# El-Fueradoro_Zuendbox_v2.net
KiCad netlist of a schematic drawn in EAGLE
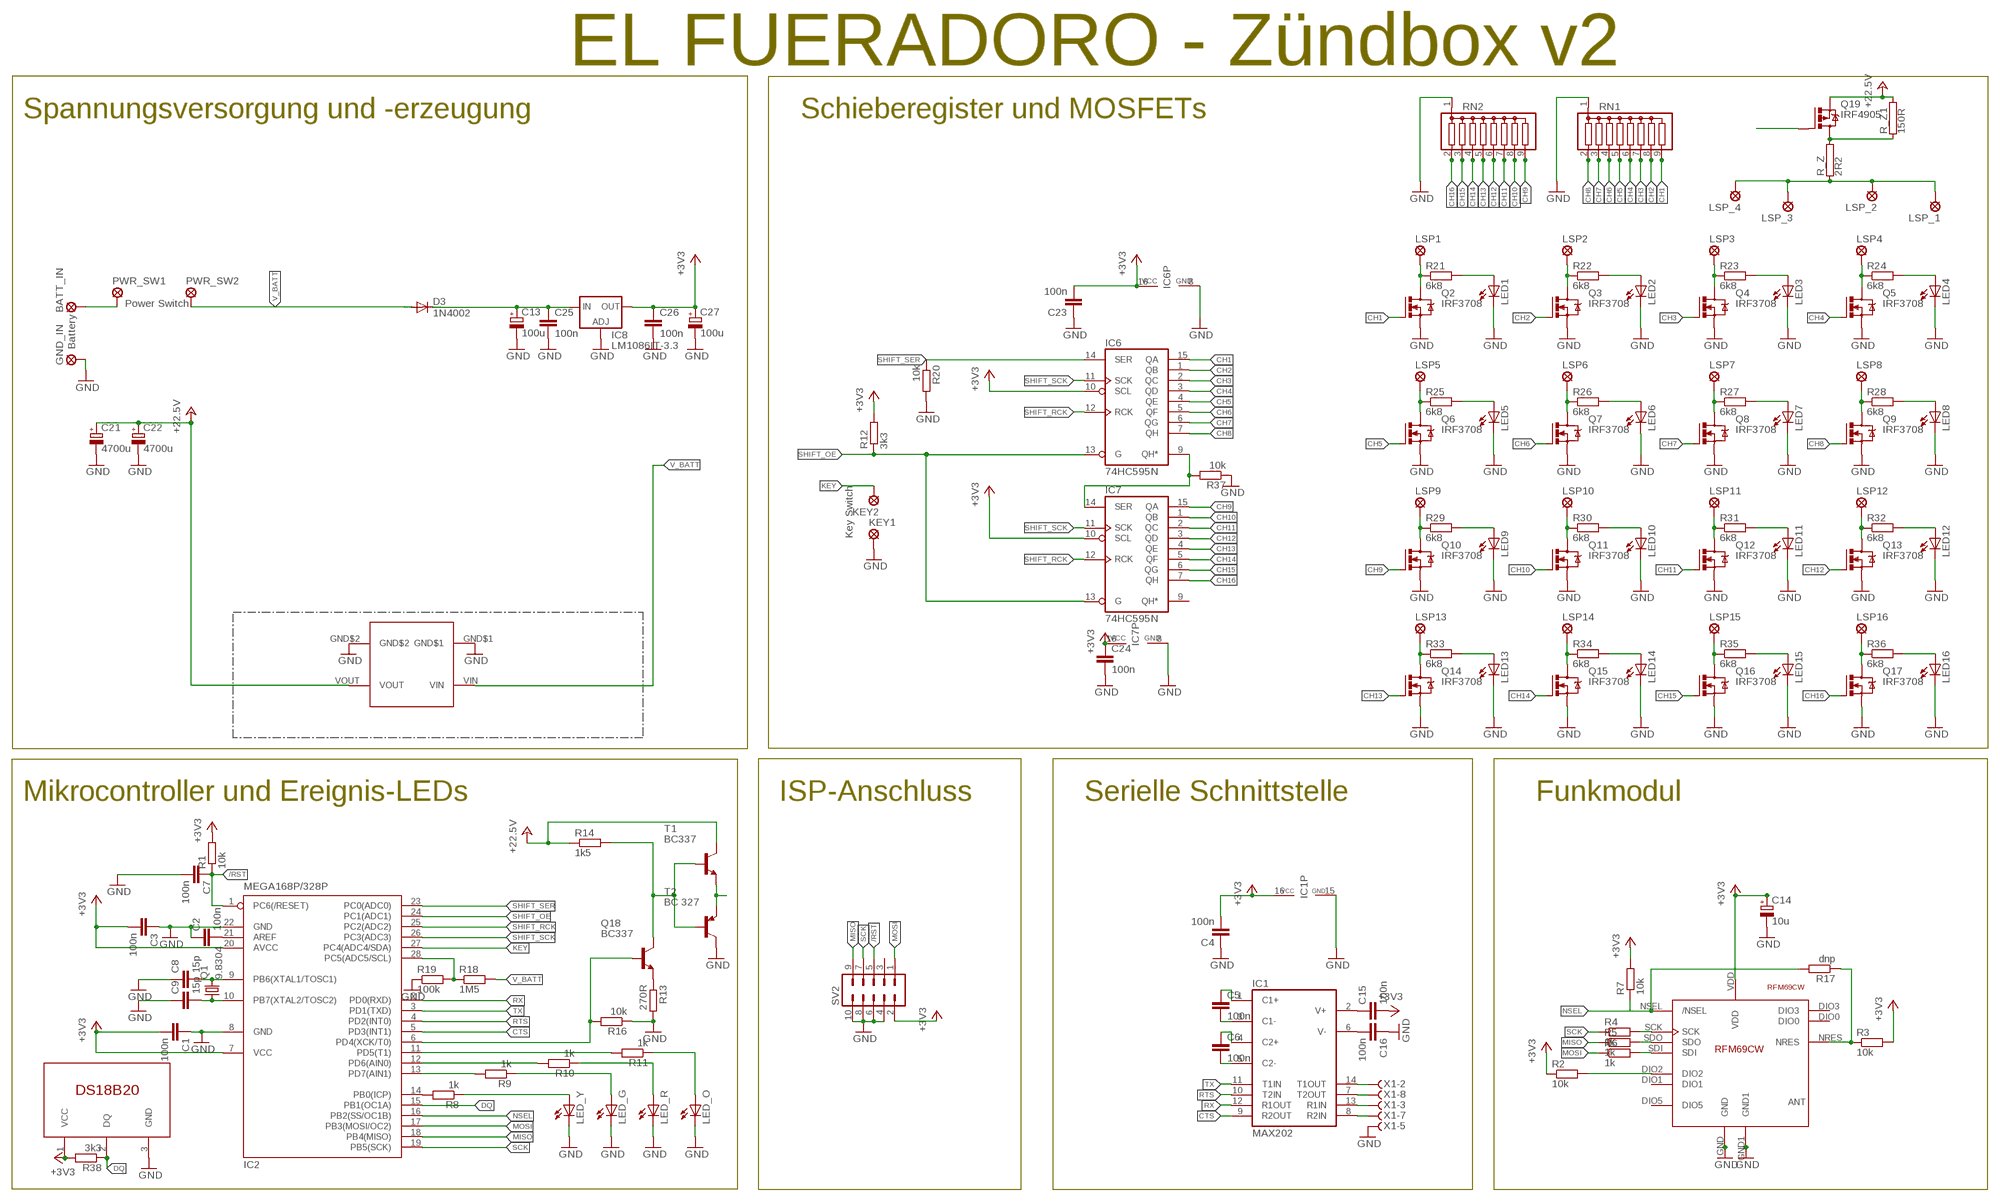
[diagram p0: schematic, sheet 1]

(export (version "E")
  (design (tool "Eeschema 10.0.6"))
  (components
    (comp (ref "BATT_IN")
      (value "LSP10")
      (footprint "eagle-import:LSP10")
      (libsource (lib "eagle-import") (part "LSP10"))
    )
    (comp (ref "C1")
      (value "100n")
      (footprint "eagle-import:C025-024X044")
      (libsource (lib "eagle-import") (part "C-EU025-024X044"))
    )
    (comp (ref "C2")
      (value "100n")
      (footprint "eagle-import:C025-024X044")
      (libsource (lib "eagle-import") (part "C-EU025-024X044"))
    )
    (comp (ref "C3")
      (value "100n")
      (footprint "eagle-import:C025-024X044")
      (libsource (lib "eagle-import") (part "C-EU025-024X044"))
    )
    (comp (ref "C4")
      (value "100n")
      (footprint "eagle-import:C025-024X044")
      (libsource (lib "eagle-import") (part "C-EU025-024X044"))
    )
    (comp (ref "C5")
      (value "100n")
      (footprint "eagle-import:C025-024X044")
      (libsource (lib "eagle-import") (part "C-EU025-024X044"))
    )
    (comp (ref "C6")
      (value "100n")
      (footprint "eagle-import:C025-024X044")
      (libsource (lib "eagle-import") (part "C-EU025-024X044"))
    )
    (comp (ref "C7")
      (value "100n")
      (footprint "eagle-import:C025-024X044")
      (libsource (lib "eagle-import") (part "C-EU025-024X044"))
    )
    (comp (ref "C8")
      (value "15p")
      (footprint "eagle-import:C025-024X044")
      (libsource (lib "eagle-import") (part "C-EU025-024X044"))
    )
    (comp (ref "C9")
      (value "15p")
      (footprint "eagle-import:C025-024X044")
      (libsource (lib "eagle-import") (part "C-EU025-024X044"))
    )
    (comp (ref "C13")
      (value "100u")
      (footprint "eagle-import:B45181A")
      (libsource (lib "eagle-import") (part "CPOL-EUB45181A"))
    )
    (comp (ref "C14")
      (value "10u")
      (footprint "eagle-import:B45181A")
      (libsource (lib "eagle-import") (part "CPOL-EUB45181A"))
    )
    (comp (ref "C15")
      (value "100n")
      (footprint "eagle-import:C025-024X044")
      (libsource (lib "eagle-import") (part "C-EU025-024X044"))
    )
    (comp (ref "C16")
      (value "100n")
      (footprint "eagle-import:C025-024X044")
      (libsource (lib "eagle-import") (part "C-EU025-024X044"))
    )
    (comp (ref "C21")
      (value "4700u")
      (footprint "eagle-import:E7,5-18")
      (libsource (lib "eagle-import") (part "CPOL-EUE7.5-18"))
    )
    (comp (ref "C22")
      (value "4700u")
      (footprint "eagle-import:E7,5-18")
      (libsource (lib "eagle-import") (part "CPOL-EUE7.5-18"))
    )
    (comp (ref "C23")
      (value "100n")
      (footprint "eagle-import:C025-024X044")
      (libsource (lib "eagle-import") (part "C-EU025-024X044"))
    )
    (comp (ref "C24")
      (value "100n")
      (footprint "eagle-import:C025-024X044")
      (libsource (lib "eagle-import") (part "C-EU025-024X044"))
    )
    (comp (ref "C25")
      (value "100n")
      (footprint "eagle-import:C025-024X044")
      (libsource (lib "eagle-import") (part "C-EU025-024X044"))
    )
    (comp (ref "C26")
      (value "100n")
      (footprint "eagle-import:C025-024X044")
      (libsource (lib "eagle-import") (part "C-EU025-024X044"))
    )
    (comp (ref "C27")
      (value "100u")
      (footprint "eagle-import:B45181A")
      (libsource (lib "eagle-import") (part "CPOL-EUB45181A"))
    )
    (comp (ref "D3")
      (value "1N4002")
      (footprint "eagle-import:DO41-10")
      (libsource (lib "eagle-import") (part "1N4004"))
    )
    (comp (ref "GND_IN")
      (value "LSP10")
      (footprint "eagle-import:LSP10")
      (libsource (lib "eagle-import") (part "LSP10"))
    )
    (comp (ref "IC1")
      (value "MAX202")
      (footprint "eagle-import:DIL16")
      (fields (field (name "MF") "MAXIM") (field (name "MPN") "MAX232ACPE+"))
      (libsource (lib "eagle-import") (part "MAX232"))
    )
    (comp (ref "IC2")
      (value "MEGA168P/328P")
      (footprint "eagle-import:DIL28-3")
      (libsource (lib "eagle-import") (part "MEGA8-P"))
    )
    (comp (ref "IC6")
      (value "74HC595N")
      (footprint "eagle-import:DIL16")
      (libsource (lib "eagle-import") (part "74595NHC"))
    )
    (comp (ref "IC7")
      (value "74HC595N")
      (footprint "eagle-import:DIL16")
      (libsource (lib "eagle-import") (part "74595NHC"))
    )
    (comp (ref "IC8")
      (value "LM1086IT-3.3")
      (footprint "eagle-import:TO220L1")
      (libsource (lib "eagle-import") (part "LD117A?V"))
    )
    (comp (ref "KEY1")
      (value "LSP10")
      (footprint "eagle-import:LSP10")
      (libsource (lib "eagle-import") (part "LSP10"))
    )
    (comp (ref "KEY2")
      (value "LSP10")
      (footprint "eagle-import:LSP10")
      (libsource (lib "eagle-import") (part "LSP10"))
    )
    (comp (ref "LED1")
      (value "LED3MM")
      (footprint "eagle-import:LED3MM")
      (libsource (lib "eagle-import") (part "LED3MM"))
    )
    (comp (ref "LED2")
      (value "LED3MM")
      (footprint "eagle-import:LED3MM")
      (libsource (lib "eagle-import") (part "LED3MM"))
    )
    (comp (ref "LED3")
      (value "LED3MM")
      (footprint "eagle-import:LED3MM")
      (libsource (lib "eagle-import") (part "LED3MM"))
    )
    (comp (ref "LED4")
      (value "LED3MM")
      (footprint "eagle-import:LED3MM")
      (libsource (lib "eagle-import") (part "LED3MM"))
    )
    (comp (ref "LED5")
      (value "LED3MM")
      (footprint "eagle-import:LED3MM")
      (libsource (lib "eagle-import") (part "LED3MM"))
    )
    (comp (ref "LED6")
      (value "LED3MM")
      (footprint "eagle-import:LED3MM")
      (libsource (lib "eagle-import") (part "LED3MM"))
    )
    (comp (ref "LED7")
      (value "LED3MM")
      (footprint "eagle-import:LED3MM")
      (libsource (lib "eagle-import") (part "LED3MM"))
    )
    (comp (ref "LED8")
      (value "LED3MM")
      (footprint "eagle-import:LED3MM")
      (libsource (lib "eagle-import") (part "LED3MM"))
    )
    (comp (ref "LED9")
      (value "LED3MM")
      (footprint "eagle-import:LED3MM")
      (libsource (lib "eagle-import") (part "LED3MM"))
    )
    (comp (ref "LED10")
      (value "LED3MM")
      (footprint "eagle-import:LED3MM")
      (libsource (lib "eagle-import") (part "LED3MM"))
    )
    (comp (ref "LED11")
      (value "LED3MM")
      (footprint "eagle-import:LED3MM")
      (libsource (lib "eagle-import") (part "LED3MM"))
    )
    (comp (ref "LED12")
      (value "LED3MM")
      (footprint "eagle-import:LED3MM")
      (libsource (lib "eagle-import") (part "LED3MM"))
    )
    (comp (ref "LED13")
      (value "LED3MM")
      (footprint "eagle-import:LED3MM")
      (libsource (lib "eagle-import") (part "LED3MM"))
    )
    (comp (ref "LED14")
      (value "LED3MM")
      (footprint "eagle-import:LED3MM")
      (libsource (lib "eagle-import") (part "LED3MM"))
    )
    (comp (ref "LED15")
      (value "LED3MM")
      (footprint "eagle-import:LED3MM")
      (libsource (lib "eagle-import") (part "LED3MM"))
    )
    (comp (ref "LED16")
      (value "LED3MM")
      (footprint "eagle-import:LED3MM")
      (libsource (lib "eagle-import") (part "LED3MM"))
    )
    (comp (ref "LED_G")
      (value "LED5MM")
      (footprint "eagle-import:LED5MM")
      (libsource (lib "eagle-import") (part "LED5MM"))
    )
    (comp (ref "LED_O")
      (value "LED5MM")
      (footprint "eagle-import:LED5MM")
      (libsource (lib "eagle-import") (part "LED5MM"))
    )
    (comp (ref "LED_R")
      (value "LED5MM")
      (footprint "eagle-import:LED5MM")
      (libsource (lib "eagle-import") (part "LED5MM"))
    )
    (comp (ref "LED_Y")
      (value "LED5MM")
      (footprint "eagle-import:LED5MM")
      (libsource (lib "eagle-import") (part "LED5MM"))
    )
    (comp (ref "LSP1")
      (value "CH1")
      (footprint "eagle-import:LSP11")
      (libsource (lib "eagle-import") (part "LSP11"))
    )
    (comp (ref "LSP2")
      (value "CH2")
      (footprint "eagle-import:LSP11")
      (libsource (lib "eagle-import") (part "LSP11"))
    )
    (comp (ref "LSP3")
      (value "CH3")
      (footprint "eagle-import:LSP11")
      (libsource (lib "eagle-import") (part "LSP11"))
    )
    (comp (ref "LSP4")
      (value "CH4")
      (footprint "eagle-import:LSP11")
      (libsource (lib "eagle-import") (part "LSP11"))
    )
    (comp (ref "LSP5")
      (value "CH5")
      (footprint "eagle-import:LSP11")
      (libsource (lib "eagle-import") (part "LSP11"))
    )
    (comp (ref "LSP6")
      (value "CH6")
      (footprint "eagle-import:LSP11")
      (libsource (lib "eagle-import") (part "LSP11"))
    )
    (comp (ref "LSP7")
      (value "CH7")
      (footprint "eagle-import:LSP11")
      (libsource (lib "eagle-import") (part "LSP11"))
    )
    (comp (ref "LSP8")
      (value "CH8")
      (footprint "eagle-import:LSP11")
      (libsource (lib "eagle-import") (part "LSP11"))
    )
    (comp (ref "LSP9")
      (value "CH9")
      (footprint "eagle-import:LSP11")
      (libsource (lib "eagle-import") (part "LSP11"))
    )
    (comp (ref "LSP10")
      (value "CH10")
      (footprint "eagle-import:LSP11")
      (libsource (lib "eagle-import") (part "LSP11"))
    )
    (comp (ref "LSP11")
      (value "CH11")
      (footprint "eagle-import:LSP11")
      (libsource (lib "eagle-import") (part "LSP11"))
    )
    (comp (ref "LSP12")
      (value "CH12")
      (footprint "eagle-import:LSP11")
      (libsource (lib "eagle-import") (part "LSP11"))
    )
    (comp (ref "LSP13")
      (value "CH13")
      (footprint "eagle-import:LSP11")
      (libsource (lib "eagle-import") (part "LSP11"))
    )
    (comp (ref "LSP14")
      (value "CH14")
      (footprint "eagle-import:LSP11")
      (libsource (lib "eagle-import") (part "LSP11"))
    )
    (comp (ref "LSP15")
      (value "CH15")
      (footprint "eagle-import:LSP11")
      (libsource (lib "eagle-import") (part "LSP11"))
    )
    (comp (ref "LSP16")
      (value "CH16")
      (footprint "eagle-import:LSP11")
      (libsource (lib "eagle-import") (part "LSP11"))
    )
    (comp (ref "LSP_1")
      (value "LSP11")
      (footprint "eagle-import:LSP11")
      (libsource (lib "eagle-import") (part "LSP11"))
    )
    (comp (ref "LSP_2")
      (value "LSP11")
      (footprint "eagle-import:LSP11")
      (libsource (lib "eagle-import") (part "LSP11"))
    )
    (comp (ref "LSP_3")
      (value "LSP11")
      (footprint "eagle-import:LSP11")
      (libsource (lib "eagle-import") (part "LSP11"))
    )
    (comp (ref "LSP_4")
      (value "LSP11")
      (footprint "eagle-import:LSP11")
      (libsource (lib "eagle-import") (part "LSP11"))
    )
    (comp (ref "PWR_SW1")
      (value "LSP10")
      (footprint "eagle-import:LSP10")
      (libsource (lib "eagle-import") (part "LSP10"))
    )
    (comp (ref "PWR_SW2")
      (value "LSP10")
      (footprint "eagle-import:LSP10")
      (libsource (lib "eagle-import") (part "LSP10"))
    )
    (comp (ref "Q1")
      (value "9.8304")
      (footprint "eagle-import:HC49_S")
      (libsource (lib "eagle-import") (part "CRYSTALHC49S"))
    )
    (comp (ref "Q2")
      (value "IRF3708")
      (footprint "eagle-import:TO220BV")
      (libsource (lib "eagle-import") (part "IRF530"))
    )
    (comp (ref "Q3")
      (value "IRF3708")
      (footprint "eagle-import:TO220BV")
      (libsource (lib "eagle-import") (part "IRF530"))
    )
    (comp (ref "Q4")
      (value "IRF3708")
      (footprint "eagle-import:TO220BV")
      (libsource (lib "eagle-import") (part "IRF530"))
    )
    (comp (ref "Q5")
      (value "IRF3708")
      (footprint "eagle-import:TO220BV")
      (libsource (lib "eagle-import") (part "IRF530"))
    )
    (comp (ref "Q6")
      (value "IRF3708")
      (footprint "eagle-import:TO220BV")
      (libsource (lib "eagle-import") (part "IRF530"))
    )
    (comp (ref "Q7")
      (value "IRF3708")
      (footprint "eagle-import:TO220BV")
      (libsource (lib "eagle-import") (part "IRF530"))
    )
    (comp (ref "Q8")
      (value "IRF3708")
      (footprint "eagle-import:TO220BV")
      (libsource (lib "eagle-import") (part "IRF530"))
    )
    (comp (ref "Q9")
      (value "IRF3708")
      (footprint "eagle-import:TO220BV")
      (libsource (lib "eagle-import") (part "IRF530"))
    )
    (comp (ref "Q10")
      (value "IRF3708")
      (footprint "eagle-import:TO220BV")
      (libsource (lib "eagle-import") (part "IRF530"))
    )
    (comp (ref "Q11")
      (value "IRF3708")
      (footprint "eagle-import:TO220BV")
      (libsource (lib "eagle-import") (part "IRF530"))
    )
    (comp (ref "Q12")
      (value "IRF3708")
      (footprint "eagle-import:TO220BV")
      (libsource (lib "eagle-import") (part "IRF530"))
    )
    (comp (ref "Q13")
      (value "IRF3708")
      (footprint "eagle-import:TO220BV")
      (libsource (lib "eagle-import") (part "IRF530"))
    )
    (comp (ref "Q14")
      (value "IRF3708")
      (footprint "eagle-import:TO220BV")
      (libsource (lib "eagle-import") (part "IRF530"))
    )
    (comp (ref "Q15")
      (value "IRF3708")
      (footprint "eagle-import:TO220BV")
      (libsource (lib "eagle-import") (part "IRF530"))
    )
    (comp (ref "Q16")
      (value "IRF3708")
      (footprint "eagle-import:TO220BV")
      (libsource (lib "eagle-import") (part "IRF530"))
    )
    (comp (ref "Q17")
      (value "IRF3708")
      (footprint "eagle-import:TO220BV")
      (libsource (lib "eagle-import") (part "IRF530"))
    )
    (comp (ref "Q18")
      (value "BC337")
      (footprint "eagle-import:TO92")
      (libsource (lib "eagle-import") (part "BC337-40"))
    )
    (comp (ref "Q19")
      (value "IRF4905")
      (footprint "eagle-import:TO220BV")
      (libsource (lib "eagle-import") (part "IRF9530"))
    )
    (comp (ref "R1")
      (value "10k")
      (footprint "eagle-import:0207_10")
      (libsource (lib "eagle-import") (part "R-EU_0207/10"))
    )
    (comp (ref "R2")
      (value "10k")
      (footprint "eagle-import:0207_10")
      (libsource (lib "eagle-import") (part "R-EU_0207/10"))
    )
    (comp (ref "R3")
      (value "10k")
      (footprint "eagle-import:0207_10")
      (libsource (lib "eagle-import") (part "R-EU_0207/10"))
    )
    (comp (ref "R4")
      (value "1k")
      (footprint "eagle-import:0207_10")
      (libsource (lib "eagle-import") (part "R-EU_0207/10"))
    )
    (comp (ref "R5")
      (value "1k")
      (footprint "eagle-import:0207_10")
      (libsource (lib "eagle-import") (part "R-EU_0207/10"))
    )
    (comp (ref "R6")
      (value "1k")
      (footprint "eagle-import:0207_10")
      (libsource (lib "eagle-import") (part "R-EU_0207/10"))
    )
    (comp (ref "R7")
      (value "10k")
      (footprint "eagle-import:0207_10")
      (libsource (lib "eagle-import") (part "R-EU_0207/10"))
    )
    (comp (ref "R8")
      (value "1k")
      (footprint "eagle-import:0207_10")
      (libsource (lib "eagle-import") (part "R-EU_0207/10"))
    )
    (comp (ref "R9")
      (value "1k")
      (footprint "eagle-import:0207_10")
      (libsource (lib "eagle-import") (part "R-EU_0207/10"))
    )
    (comp (ref "R10")
      (value "1k")
      (footprint "eagle-import:0207_10")
      (libsource (lib "eagle-import") (part "R-EU_0207/10"))
    )
    (comp (ref "R11")
      (value "1k")
      (footprint "eagle-import:0207_10")
      (libsource (lib "eagle-import") (part "R-EU_0207/10"))
    )
    (comp (ref "R12")
      (value "3k3")
      (footprint "eagle-import:0207_10")
      (libsource (lib "eagle-import") (part "R-EU_0207/10"))
    )
    (comp (ref "R13")
      (value "270R")
      (footprint "eagle-import:0207_10")
      (libsource (lib "eagle-import") (part "R-EU_0207/10"))
    )
    (comp (ref "R14")
      (value "1k5")
      (footprint "eagle-import:0207_10")
      (libsource (lib "eagle-import") (part "R-EU_0207/10"))
    )
    (comp (ref "R16")
      (value "10k")
      (footprint "eagle-import:0207_10")
      (libsource (lib "eagle-import") (part "R-EU_0207/10"))
    )
    (comp (ref "R17")
      (value "dnp")
      (footprint "eagle-import:0207_10")
      (libsource (lib "eagle-import") (part "R-EU_0207/10"))
    )
    (comp (ref "R18")
      (value "1M5")
      (footprint "eagle-import:0207_10")
      (libsource (lib "eagle-import") (part "R-EU_0207/10"))
    )
    (comp (ref "R19")
      (value "100k")
      (footprint "eagle-import:0207_10")
      (libsource (lib "eagle-import") (part "R-EU_0207/10"))
    )
    (comp (ref "R20")
      (value "10k")
      (footprint "eagle-import:0207_10")
      (libsource (lib "eagle-import") (part "R-EU_0207/10"))
    )
    (comp (ref "R21")
      (value "6k8")
      (footprint "eagle-import:0207_10")
      (libsource (lib "eagle-import") (part "R-EU_0207/10"))
    )
    (comp (ref "R22")
      (value "6k8")
      (footprint "eagle-import:0207_10")
      (libsource (lib "eagle-import") (part "R-EU_0207/10"))
    )
    (comp (ref "R23")
      (value "6k8")
      (footprint "eagle-import:0207_10")
      (libsource (lib "eagle-import") (part "R-EU_0207/10"))
    )
    (comp (ref "R24")
      (value "6k8")
      (footprint "eagle-import:0207_10")
      (libsource (lib "eagle-import") (part "R-EU_0207/10"))
    )
    (comp (ref "R25")
      (value "6k8")
      (footprint "eagle-import:0207_10")
      (libsource (lib "eagle-import") (part "R-EU_0207/10"))
    )
    (comp (ref "R26")
      (value "6k8")
      (footprint "eagle-import:0207_10")
      (libsource (lib "eagle-import") (part "R-EU_0207/10"))
    )
    (comp (ref "R27")
      (value "6k8")
      (footprint "eagle-import:0207_10")
      (libsource (lib "eagle-import") (part "R-EU_0207/10"))
    )
    (comp (ref "R28")
      (value "6k8")
      (footprint "eagle-import:0207_10")
      (libsource (lib "eagle-import") (part "R-EU_0207/10"))
    )
    (comp (ref "R29")
      (value "6k8")
      (footprint "eagle-import:0207_10")
      (libsource (lib "eagle-import") (part "R-EU_0207/10"))
    )
    (comp (ref "R30")
      (value "6k8")
      (footprint "eagle-import:0207_10")
      (libsource (lib "eagle-import") (part "R-EU_0207/10"))
    )
    (comp (ref "R31")
      (value "6k8")
      (footprint "eagle-import:0207_10")
      (libsource (lib "eagle-import") (part "R-EU_0207/10"))
    )
    (comp (ref "R32")
      (value "6k8")
      (footprint "eagle-import:0207_10")
      (libsource (lib "eagle-import") (part "R-EU_0207/10"))
    )
    (comp (ref "R33")
      (value "6k8")
      (footprint "eagle-import:0207_10")
      (libsource (lib "eagle-import") (part "R-EU_0207/10"))
    )
    (comp (ref "R34")
      (value "6k8")
      (footprint "eagle-import:0207_10")
      (libsource (lib "eagle-import") (part "R-EU_0207/10"))
    )
    (comp (ref "R35")
      (value "6k8")
      (footprint "eagle-import:0207_10")
      (libsource (lib "eagle-import") (part "R-EU_0207/10"))
    )
    (comp (ref "R36")
      (value "6k8")
      (footprint "eagle-import:0207_10")
      (libsource (lib "eagle-import") (part "R-EU_0207/10"))
    )
    (comp (ref "R37")
      (value "10k")
      (footprint "eagle-import:0207_10")
      (libsource (lib "eagle-import") (part "R-EU_0207/10"))
    )
    (comp (ref "R38")
      (value "3k3")
      (footprint "eagle-import:0207_10")
      (libsource (lib "eagle-import") (part "R-EU_0207/10"))
    )
    (comp (ref "RN1")
      (value "G08R")
      (footprint "eagle-import:SIL9")
      (libsource (lib "eagle-import") (part "G08R"))
    )
    (comp (ref "RN2")
      (value "G08R")
      (footprint "eagle-import:SIL9")
      (libsource (lib "eagle-import") (part "G08R"))
    )
    (comp (ref "R_Z")
      (value "2R2")
      (footprint "eagle-import:KH214R-8")
      (libsource (lib "eagle-import") (part "RKH214-8R"))
    )
    (comp (ref "R_Z1")
      (value "150R")
      (footprint "eagle-import:KH214R-8")
      (libsource (lib "eagle-import") (part "RKH214-8R"))
    )
    (comp (ref "SV2")
      (value "ML10")
      (footprint "eagle-import:ML10")
      (libsource (lib "eagle-import") (part "ML10"))
    )
    (comp (ref "T1")
      (value "BC337")
      (footprint "eagle-import:TO92")
      (libsource (lib "eagle-import") (part "BC337"))
    )
    (comp (ref "T2")
      (value "BC 327")
      (footprint "eagle-import:TO92")
      (libsource (lib "eagle-import") (part "BC327"))
    )
    (comp (ref "U$2")
      (value "DS18B20")
      (footprint "eagle-import:TO92-LINE")
      (libsource (lib "eagle-import") (part "DS18B20"))
    )
    (comp (ref "U$3")
      (value "XL6009_MODULED")
      (footprint "eagle-import:XL6009_PACK")
      (libsource (lib "eagle-import") (part "XL6009_MODULED"))
    )
    (comp (ref "U$4")
      (value "RFM69CW")
      (footprint "eagle-import:RFM69CW")
      (libsource (lib "eagle-import") (part "RFM69CW"))
    )
    (comp (ref "X1")
      (value "F09HPS")
      (footprint "eagle-import:F09HP")
      (libsource (lib "eagle-import") (part "F09HPS"))
    )
  )
  (nets
    (net (code "1") (name "+3V3") (class "Default")
      (node (ref "C1") (pin "2") (pinfunction "2_2") (pintype "passive"))
      (node (ref "C14") (pin "+") (pinfunction "+_+") (pintype "passive"))
      (node (ref "C15") (pin "2") (pinfunction "2_2") (pintype "passive"))
      (node (ref "C23") (pin "2") (pinfunction "2_2") (pintype "passive"))
      (node (ref "C24") (pin "1") (pinfunction "1_1") (pintype "passive"))
      (node (ref "C26") (pin "1") (pinfunction "1_1") (pintype "passive"))
      (node (ref "C27") (pin "+") (pinfunction "+_+") (pintype "passive"))
      (node (ref "C3") (pin "2") (pinfunction "2_2") (pintype "passive"))
      (node (ref "C4") (pin "2") (pinfunction "2_2") (pintype "passive"))
      (node (ref "IC1") (pin "16") (pinfunction "VCC_16") (pintype "power_in"))
      (node (ref "IC2") (pin "20") (pinfunction "AVCC_20") (pintype "power_in"))
      (node (ref "IC2") (pin "7") (pinfunction "VCC_7") (pintype "power_in"))
      (node (ref "IC6") (pin "10") (pinfunction "SCL_10") (pintype "input"))
      (node (ref "IC6") (pin "16") (pinfunction "VCC_16") (pintype "power_in"))
      (node (ref "IC7") (pin "10") (pinfunction "SCL_10") (pintype "input"))
      (node (ref "IC7") (pin "16") (pinfunction "VCC_16") (pintype "power_in"))
      (node (ref "IC8") (pin "2") (pinfunction "OUT_2") (pintype "passive"))
      (node (ref "R1") (pin "2") (pinfunction "2_2") (pintype "passive"))
      (node (ref "R12") (pin "2") (pinfunction "2_2") (pintype "passive"))
      (node (ref "R2") (pin "1") (pinfunction "1_1") (pintype "passive"))
      (node (ref "R3") (pin "2") (pinfunction "2_2") (pintype "passive"))
      (node (ref "R38") (pin "2") (pinfunction "2_2") (pintype "passive"))
      (node (ref "R7") (pin "2") (pinfunction "2_2") (pintype "passive"))
      (node (ref "SV2") (pin "2") (pinfunction "2_2") (pintype "passive"))
      (node (ref "U$2") (pin "1") (pinfunction "VCC_1") (pintype "power_in"))
      (node (ref "U$4") (pin "VDD") (pinfunction "VDD_VDD") (pintype "power_in"))
    )
    (net (code "2") (name "+22.5V") (class "Default")
      (node (ref "C21") (pin "+") (pinfunction "+_+") (pintype "passive"))
      (node (ref "C22") (pin "+") (pinfunction "+_+") (pintype "passive"))
      (node (ref "Q19") (pin "S") (pinfunction "S_S") (pintype "passive"))
      (node (ref "R14") (pin "1") (pinfunction "1_1") (pintype "passive"))
      (node (ref "R_Z1") (pin "2") (pinfunction "2_2") (pintype "passive"))
      (node (ref "T1") (pin "3") (pinfunction "C_3") (pintype "passive"))
      (node (ref "U$3") (pin "VOUT") (pinfunction "VOUT_VOUT") (pintype "bidirectional"))
    )
    (net (code "3") (name "/PMOSG") (class "Default")
      (node (ref "Q19") (pin "G") (pinfunction "G_G") (pintype "passive"))
      (node (ref "T1") (pin "1") (pinfunction "E_1") (pintype "passive"))
      (node (ref "T2") (pin "1") (pinfunction "E_1") (pintype "passive"))
    )
    (net (code "4") (name "CH1") (class "Default")
      (node (ref "IC6") (pin "15") (pinfunction "QA_15") (pintype "tri_state"))
      (node (ref "Q2") (pin "G") (pinfunction "G_G") (pintype "passive"))
      (node (ref "RN1") (pin "9") (pinfunction "9_9") (pintype "passive"))
    )
    (net (code "5") (name "CH2") (class "Default")
      (node (ref "IC6") (pin "1") (pinfunction "QB_1") (pintype "tri_state"))
      (node (ref "Q3") (pin "G") (pinfunction "G_G") (pintype "passive"))
      (node (ref "RN1") (pin "8") (pinfunction "8_8") (pintype "passive"))
    )
    (net (code "6") (name "CH3") (class "Default")
      (node (ref "IC6") (pin "2") (pinfunction "QC_2") (pintype "tri_state"))
      (node (ref "Q4") (pin "G") (pinfunction "G_G") (pintype "passive"))
      (node (ref "RN1") (pin "7") (pinfunction "7_7") (pintype "passive"))
    )
    (net (code "7") (name "CH4") (class "Default")
      (node (ref "IC6") (pin "3") (pinfunction "QD_3") (pintype "tri_state"))
      (node (ref "Q5") (pin "G") (pinfunction "G_G") (pintype "passive"))
      (node (ref "RN1") (pin "6") (pinfunction "6_6") (pintype "passive"))
    )
    (net (code "8") (name "CH5") (class "Default")
      (node (ref "IC6") (pin "4") (pinfunction "QE_4") (pintype "tri_state"))
      (node (ref "Q6") (pin "G") (pinfunction "G_G") (pintype "passive"))
      (node (ref "RN1") (pin "5") (pinfunction "5_5") (pintype "passive"))
    )
    (net (code "9") (name "CH6") (class "Default")
      (node (ref "IC6") (pin "5") (pinfunction "QF_5") (pintype "tri_state"))
      (node (ref "Q7") (pin "G") (pinfunction "G_G") (pintype "passive"))
      (node (ref "RN1") (pin "4") (pinfunction "4_4") (pintype "passive"))
    )
    (net (code "10") (name "CH7") (class "Default")
      (node (ref "IC6") (pin "6") (pinfunction "QG_6") (pintype "tri_state"))
      (node (ref "Q8") (pin "G") (pinfunction "G_G") (pintype "passive"))
      (node (ref "RN1") (pin "3") (pinfunction "3_3") (pintype "passive"))
    )
    (net (code "11") (name "CH8") (class "Default")
      (node (ref "IC6") (pin "7") (pinfunction "QH_7") (pintype "tri_state"))
      (node (ref "Q9") (pin "G") (pinfunction "G_G") (pintype "passive"))
      (node (ref "RN1") (pin "2") (pinfunction "2_2") (pintype "passive"))
    )
    (net (code "12") (name "CH9") (class "Default")
      (node (ref "IC7") (pin "15") (pinfunction "QA_15") (pintype "tri_state"))
      (node (ref "Q10") (pin "G") (pinfunction "G_G") (pintype "passive"))
      (node (ref "RN2") (pin "9") (pinfunction "9_9") (pintype "passive"))
    )
    (net (code "13") (name "CH10") (class "Default")
      (node (ref "IC7") (pin "1") (pinfunction "QB_1") (pintype "tri_state"))
      (node (ref "Q11") (pin "G") (pinfunction "G_G") (pintype "passive"))
      (node (ref "RN2") (pin "8") (pinfunction "8_8") (pintype "passive"))
    )
    (net (code "14") (name "CH11") (class "Default")
      (node (ref "IC7") (pin "2") (pinfunction "QC_2") (pintype "tri_state"))
      (node (ref "Q12") (pin "G") (pinfunction "G_G") (pintype "passive"))
      (node (ref "RN2") (pin "7") (pinfunction "7_7") (pintype "passive"))
    )
    (net (code "15") (name "CH12") (class "Default")
      (node (ref "IC7") (pin "3") (pinfunction "QD_3") (pintype "tri_state"))
      (node (ref "Q13") (pin "G") (pinfunction "G_G") (pintype "passive"))
      (node (ref "RN2") (pin "6") (pinfunction "6_6") (pintype "passive"))
    )
    (net (code "16") (name "CH13") (class "Default")
      (node (ref "IC7") (pin "4") (pinfunction "QE_4") (pintype "tri_state"))
      (node (ref "Q14") (pin "G") (pinfunction "G_G") (pintype "passive"))
      (node (ref "RN2") (pin "5") (pinfunction "5_5") (pintype "passive"))
    )
    (net (code "17") (name "CH14") (class "Default")
      (node (ref "IC7") (pin "5") (pinfunction "QF_5") (pintype "tri_state"))
      (node (ref "Q15") (pin "G") (pinfunction "G_G") (pintype "passive"))
      (node (ref "RN2") (pin "4") (pinfunction "4_4") (pintype "passive"))
    )
    (net (code "18") (name "CH15") (class "Default")
      (node (ref "IC7") (pin "6") (pinfunction "QG_6") (pintype "tri_state"))
      (node (ref "Q16") (pin "G") (pinfunction "G_G") (pintype "passive"))
      (node (ref "RN2") (pin "3") (pinfunction "3_3") (pintype "passive"))
    )
    (net (code "19") (name "CH16") (class "Default")
      (node (ref "IC7") (pin "7") (pinfunction "QH_7") (pintype "tri_state"))
      (node (ref "Q17") (pin "G") (pinfunction "G_G") (pintype "passive"))
      (node (ref "RN2") (pin "2") (pinfunction "2_2") (pintype "passive"))
    )
    (net (code "20") (name "CTS") (class "Default")
      (node (ref "IC1") (pin "9") (pinfunction "R2OUT_9") (pintype "output"))
      (node (ref "IC2") (pin "5") (pinfunction "PD3(INT1)_5") (pintype "bidirectional"))
    )
    (net (code "21") (name "DQ") (class "Default")
      (node (ref "IC2") (pin "15") (pinfunction "PB1(OC1A)_15") (pintype "bidirectional"))
      (node (ref "R38") (pin "1") (pinfunction "1_1") (pintype "passive"))
      (node (ref "U$2") (pin "2") (pinfunction "DQ_2") (pintype "bidirectional"))
    )
    (net (code "22") (name "GND") (class "Default")
      (node (ref "C1") (pin "1") (pinfunction "1_1") (pintype "passive"))
      (node (ref "C13") (pin "-") (pinfunction "-_-") (pintype "passive"))
      (node (ref "C14") (pin "-") (pinfunction "-_-") (pintype "passive"))
      (node (ref "C16") (pin "1") (pinfunction "1_1") (pintype "passive"))
      (node (ref "C2") (pin "1") (pinfunction "1_1") (pintype "passive"))
      (node (ref "C21") (pin "-") (pinfunction "-_-") (pintype "passive"))
      (node (ref "C22") (pin "-") (pinfunction "-_-") (pintype "passive"))
      (node (ref "C23") (pin "1") (pinfunction "1_1") (pintype "passive"))
      (node (ref "C24") (pin "2") (pinfunction "2_2") (pintype "passive"))
      (node (ref "C25") (pin "2") (pinfunction "2_2") (pintype "passive"))
      (node (ref "C26") (pin "2") (pinfunction "2_2") (pintype "passive"))
      (node (ref "C27") (pin "-") (pinfunction "-_-") (pintype "passive"))
      (node (ref "C3") (pin "1") (pinfunction "1_1") (pintype "passive"))
      (node (ref "C4") (pin "1") (pinfunction "1_1") (pintype "passive"))
      (node (ref "C7") (pin "2") (pinfunction "2_2") (pintype "passive"))
      (node (ref "C8") (pin "1") (pinfunction "1_1") (pintype "passive"))
      (node (ref "C9") (pin "1") (pinfunction "1_1") (pintype "passive"))
      (node (ref "GND_IN") (pin "MP") (pinfunction "MP_MP") (pintype "passive"))
      (node (ref "IC1") (pin "15") (pinfunction "GND_15") (pintype "power_in"))
      (node (ref "IC2") (pin "22") (pinfunction "GND_22") (pintype "power_in"))
      (node (ref "IC2") (pin "8") (pinfunction "GND_8") (pintype "power_in"))
      (node (ref "IC6") (pin "8") (pinfunction "GND_8") (pintype "power_in"))
      (node (ref "IC7") (pin "8") (pinfunction "GND_8") (pintype "power_in"))
      (node (ref "IC8") (pin "1") (pinfunction "ADJ_1") (pintype "input"))
      (node (ref "KEY1") (pin "MP") (pinfunction "MP_MP") (pintype "passive"))
      (node (ref "LED1") (pin "K") (pinfunction "C_K") (pintype "passive"))
      (node (ref "LED10") (pin "K") (pinfunction "C_K") (pintype "passive"))
      (node (ref "LED11") (pin "K") (pinfunction "C_K") (pintype "passive"))
      (node (ref "LED12") (pin "K") (pinfunction "C_K") (pintype "passive"))
      (node (ref "LED13") (pin "K") (pinfunction "C_K") (pintype "passive"))
      (node (ref "LED14") (pin "K") (pinfunction "C_K") (pintype "passive"))
      (node (ref "LED15") (pin "K") (pinfunction "C_K") (pintype "passive"))
      (node (ref "LED16") (pin "K") (pinfunction "C_K") (pintype "passive"))
      (node (ref "LED2") (pin "K") (pinfunction "C_K") (pintype "passive"))
      (node (ref "LED3") (pin "K") (pinfunction "C_K") (pintype "passive"))
      (node (ref "LED4") (pin "K") (pinfunction "C_K") (pintype "passive"))
      (node (ref "LED5") (pin "K") (pinfunction "C_K") (pintype "passive"))
      (node (ref "LED6") (pin "K") (pinfunction "C_K") (pintype "passive"))
      (node (ref "LED7") (pin "K") (pinfunction "C_K") (pintype "passive"))
      (node (ref "LED8") (pin "K") (pinfunction "C_K") (pintype "passive"))
      (node (ref "LED9") (pin "K") (pinfunction "C_K") (pintype "passive"))
      (node (ref "LED_G") (pin "K") (pinfunction "C_K") (pintype "passive"))
      (node (ref "LED_O") (pin "K") (pinfunction "C_K") (pintype "passive"))
      (node (ref "LED_R") (pin "K") (pinfunction "C_K") (pintype "passive"))
      (node (ref "LED_Y") (pin "K") (pinfunction "C_K") (pintype "passive"))
      (node (ref "Q10") (pin "S") (pinfunction "S_S") (pintype "passive"))
      (node (ref "Q11") (pin "S") (pinfunction "S_S") (pintype "passive"))
      (node (ref "Q12") (pin "S") (pinfunction "S_S") (pintype "passive"))
      (node (ref "Q13") (pin "S") (pinfunction "S_S") (pintype "passive"))
      (node (ref "Q14") (pin "S") (pinfunction "S_S") (pintype "passive"))
      (node (ref "Q15") (pin "S") (pinfunction "S_S") (pintype "passive"))
      (node (ref "Q16") (pin "S") (pinfunction "S_S") (pintype "passive"))
      (node (ref "Q17") (pin "S") (pinfunction "S_S") (pintype "passive"))
      (node (ref "Q2") (pin "S") (pinfunction "S_S") (pintype "passive"))
      (node (ref "Q3") (pin "S") (pinfunction "S_S") (pintype "passive"))
      (node (ref "Q4") (pin "S") (pinfunction "S_S") (pintype "passive"))
      (node (ref "Q5") (pin "S") (pinfunction "S_S") (pintype "passive"))
      (node (ref "Q6") (pin "S") (pinfunction "S_S") (pintype "passive"))
      (node (ref "Q7") (pin "S") (pinfunction "S_S") (pintype "passive"))
      (node (ref "Q8") (pin "S") (pinfunction "S_S") (pintype "passive"))
      (node (ref "Q9") (pin "S") (pinfunction "S_S") (pintype "passive"))
      (node (ref "R13") (pin "2") (pinfunction "2_2") (pintype "passive"))
      (node (ref "R16") (pin "1") (pinfunction "1_1") (pintype "passive"))
      (node (ref "R19") (pin "1") (pinfunction "1_1") (pintype "passive"))
      (node (ref "R20") (pin "2") (pinfunction "2_2") (pintype "passive"))
      (node (ref "R37") (pin "1") (pinfunction "1_1") (pintype "passive"))
      (node (ref "RN1") (pin "1") (pinfunction "1_1") (pintype "passive"))
      (node (ref "RN2") (pin "1") (pinfunction "1_1") (pintype "passive"))
      (node (ref "SV2") (pin "10") (pinfunction "10_10") (pintype "passive"))
      (node (ref "SV2") (pin "4") (pinfunction "4_4") (pintype "passive"))
      (node (ref "SV2") (pin "6") (pinfunction "6_6") (pintype "passive"))
      (node (ref "SV2") (pin "8") (pinfunction "8_8") (pintype "passive"))
      (node (ref "T2") (pin "3") (pinfunction "C_3") (pintype "passive"))
      (node (ref "U$2") (pin "3") (pinfunction "GND_3") (pintype "power_in"))
      (node (ref "U$3") (pin "GND$1") (pinfunction "GND$1_GND$1") (pintype "bidirectional"))
      (node (ref "U$3") (pin "GND$2") (pinfunction "GND$2_GND$2") (pintype "bidirectional"))
      (node (ref "U$4") (pin "GND") (pinfunction "GND_GND") (pintype "power_in"))
      (node (ref "U$4") (pin "GND1") (pinfunction "GND1_GND1") (pintype "power_in"))
      (node (ref "X1") (pin "5") (pinfunction "F_5") (pintype "passive"))
    )
    (net (code "23") (name "KEY") (class "Default")
      (node (ref "IC2") (pin "27") (pinfunction "PC4(ADC4/SDA)_27") (pintype "bidirectional"))
      (node (ref "KEY2") (pin "MP") (pinfunction "MP_MP") (pintype "passive"))
    )
    (net (code "24") (name "MISO") (class "Default")
      (node (ref "IC2") (pin "18") (pinfunction "PB4(MISO)_18") (pintype "bidirectional"))
      (node (ref "R5") (pin "1") (pinfunction "1_1") (pintype "passive"))
      (node (ref "SV2") (pin "9") (pinfunction "9_9") (pintype "passive"))
    )
    (net (code "25") (name "MOSI") (class "Default")
      (node (ref "IC2") (pin "17") (pinfunction "PB3(MOSI/OC2)_17") (pintype "bidirectional"))
      (node (ref "R6") (pin "1") (pinfunction "1_1") (pintype "passive"))
      (node (ref "SV2") (pin "1") (pinfunction "1_1") (pintype "passive"))
    )
    (net (code "26") (name "NSEL") (class "Default")
      (node (ref "IC2") (pin "16") (pinfunction "PB2(SS/OC1B)_16") (pintype "bidirectional"))
      (node (ref "R17") (pin "2") (pinfunction "2_2") (pintype "passive"))
      (node (ref "R7") (pin "1") (pinfunction "1_1") (pintype "passive"))
      (node (ref "U$4") (pin "NSEL") (pinfunction "/NSEL_NSEL") (pintype "input"))
    )
    (net (code "27") (name "Net-(BATT_IN-PadMP)") (class "Default")
      (node (ref "BATT_IN") (pin "MP") (pinfunction "MP_MP") (pintype "passive"))
      (node (ref "PWR_SW1") (pin "MP") (pinfunction "MP_MP") (pintype "passive"))
    )
    (net (code "28") (name "Net-(IC1A-C1+)") (class "Default")
      (node (ref "C5") (pin "1") (pinfunction "1_1") (pintype "passive"))
      (node (ref "IC1") (pin "1") (pinfunction "C1+_1") (pintype "bidirectional"))
    )
    (net (code "29") (name "Net-(IC1A-C1-)") (class "Default")
      (node (ref "C5") (pin "2") (pinfunction "2_2") (pintype "passive"))
      (node (ref "IC1") (pin "3") (pinfunction "C1-_3") (pintype "bidirectional"))
    )
    (net (code "30") (name "Net-(IC1A-C2+)") (class "Default")
      (node (ref "C6") (pin "1") (pinfunction "1_1") (pintype "passive"))
      (node (ref "IC1") (pin "4") (pinfunction "C2+_4") (pintype "bidirectional"))
    )
    (net (code "31") (name "Net-(IC1A-C2-)") (class "Default")
      (node (ref "C6") (pin "2") (pinfunction "2_2") (pintype "passive"))
      (node (ref "IC1") (pin "5") (pinfunction "C2-_5") (pintype "bidirectional"))
    )
    (net (code "32") (name "Net-(IC1A-R1IN)") (class "Default")
      (node (ref "IC1") (pin "13") (pinfunction "R1IN_13") (pintype "input"))
      (node (ref "X1") (pin "3") (pinfunction "F_3") (pintype "passive"))
    )
    (net (code "33") (name "Net-(IC1A-R2IN)") (class "Default")
      (node (ref "IC1") (pin "8") (pinfunction "R2IN_8") (pintype "input"))
      (node (ref "X1") (pin "7") (pinfunction "F_7") (pintype "passive"))
    )
    (net (code "34") (name "Net-(IC1A-T1OUT)") (class "Default")
      (node (ref "IC1") (pin "14") (pinfunction "T1OUT_14") (pintype "output"))
      (node (ref "X1") (pin "2") (pinfunction "F_2") (pintype "passive"))
    )
    (net (code "35") (name "Net-(IC1A-T2OUT)") (class "Default")
      (node (ref "IC1") (pin "7") (pinfunction "T2OUT_7") (pintype "output"))
      (node (ref "X1") (pin "8") (pinfunction "F_8") (pintype "passive"))
    )
    (net (code "36") (name "Net-(IC1A-V+)") (class "Default")
      (node (ref "C15") (pin "1") (pinfunction "1_1") (pintype "passive"))
      (node (ref "IC1") (pin "2") (pinfunction "V+_2") (pintype "bidirectional"))
    )
    (net (code "37") (name "Net-(IC1A-V-)") (class "Default")
      (node (ref "C16") (pin "2") (pinfunction "2_2") (pintype "passive"))
      (node (ref "IC1") (pin "6") (pinfunction "V-_6") (pintype "bidirectional"))
    )
    (net (code "38") (name "Net-(IC2-AREF)") (class "Default")
      (node (ref "C2") (pin "2") (pinfunction "2_2") (pintype "passive"))
      (node (ref "IC2") (pin "21") (pinfunction "AREF_21") (pintype "passive"))
    )
    (net (code "39") (name "Net-(IC2-PB0(ICP))") (class "Default")
      (node (ref "IC2") (pin "14") (pinfunction "PB0(ICP)_14") (pintype "bidirectional"))
      (node (ref "R8") (pin "2") (pinfunction "2_2") (pintype "passive"))
    )
    (net (code "40") (name "Net-(IC2-PB6(XTAL1{slash}TOSC1))") (class "Default")
      (node (ref "C8") (pin "2") (pinfunction "2_2") (pintype "passive"))
      (node (ref "IC2") (pin "9") (pinfunction "PB6(XTAL1/TOSC1)_9") (pintype "bidirectional"))
      (node (ref "Q1") (pin "2") (pinfunction "2_2") (pintype "passive"))
    )
    (net (code "41") (name "Net-(IC2-PB7(XTAL2{slash}TOSC2))") (class "Default")
      (node (ref "C9") (pin "2") (pinfunction "2_2") (pintype "passive"))
      (node (ref "IC2") (pin "10") (pinfunction "PB7(XTAL2/TOSC2)_10") (pintype "bidirectional"))
      (node (ref "Q1") (pin "1") (pinfunction "1_1") (pintype "passive"))
    )
    (net (code "42") (name "Net-(IC2-PC5(ADC5{slash}SCL))") (class "Default")
      (node (ref "IC2") (pin "28") (pinfunction "PC5(ADC5/SCL)_28") (pintype "bidirectional"))
      (node (ref "R18") (pin "1") (pinfunction "1_1") (pintype "passive"))
      (node (ref "R19") (pin "2") (pinfunction "2_2") (pintype "passive"))
    )
    (net (code "43") (name "Net-(IC2-PD4(XCK{slash}T0))") (class "Default")
      (node (ref "IC2") (pin "6") (pinfunction "PD4(XCK/T0)_6") (pintype "bidirectional"))
      (node (ref "Q18") (pin "2") (pinfunction "B_2") (pintype "passive"))
      (node (ref "R16") (pin "2") (pinfunction "2_2") (pintype "passive"))
    )
    (net (code "44") (name "Net-(IC2-PD5(T1))") (class "Default")
      (node (ref "IC2") (pin "11") (pinfunction "PD5(T1)_11") (pintype "bidirectional"))
      (node (ref "R11") (pin "2") (pinfunction "2_2") (pintype "passive"))
    )
    (net (code "45") (name "Net-(IC2-PD6(AIN0))") (class "Default")
      (node (ref "IC2") (pin "12") (pinfunction "PD6(AIN0)_12") (pintype "bidirectional"))
      (node (ref "R10") (pin "2") (pinfunction "2_2") (pintype "passive"))
    )
    (net (code "46") (name "Net-(IC2-PD7(AIN1))") (class "Default")
      (node (ref "IC2") (pin "13") (pinfunction "PD7(AIN1)_13") (pintype "bidirectional"))
      (node (ref "R9") (pin "2") (pinfunction "2_2") (pintype "passive"))
    )
    (net (code "47") (name "Net-(IC6A-QH*)") (class "Default")
      (node (ref "IC6") (pin "9") (pinfunction "QH*_9") (pintype "tri_state"))
      (node (ref "IC7") (pin "14") (pinfunction "SER_14") (pintype "input"))
      (node (ref "R37") (pin "2") (pinfunction "2_2") (pintype "passive"))
    )
    (net (code "48") (name "Net-(IC8-IN)") (class "Default")
      (node (ref "C13") (pin "+") (pinfunction "+_+") (pintype "passive"))
      (node (ref "C25") (pin "1") (pinfunction "1_1") (pintype "passive"))
      (node (ref "D3") (pin "C") (pinfunction "C_C") (pintype "passive"))
      (node (ref "IC8") (pin "3") (pinfunction "IN_3") (pintype "input"))
    )
    (net (code "49") (name "Net-(LED1-PadA)") (class "Default")
      (node (ref "LED1") (pin "A") (pinfunction "A_A") (pintype "passive"))
      (node (ref "R21") (pin "2") (pinfunction "2_2") (pintype "passive"))
    )
    (net (code "50") (name "Net-(LED2-PadA)") (class "Default")
      (node (ref "LED2") (pin "A") (pinfunction "A_A") (pintype "passive"))
      (node (ref "R22") (pin "2") (pinfunction "2_2") (pintype "passive"))
    )
    (net (code "51") (name "Net-(LED3-PadA)") (class "Default")
      (node (ref "LED3") (pin "A") (pinfunction "A_A") (pintype "passive"))
      (node (ref "R23") (pin "2") (pinfunction "2_2") (pintype "passive"))
    )
    (net (code "52") (name "Net-(LED4-PadA)") (class "Default")
      (node (ref "LED4") (pin "A") (pinfunction "A_A") (pintype "passive"))
      (node (ref "R24") (pin "2") (pinfunction "2_2") (pintype "passive"))
    )
    (net (code "53") (name "Net-(LED5-PadA)") (class "Default")
      (node (ref "LED5") (pin "A") (pinfunction "A_A") (pintype "passive"))
      (node (ref "R25") (pin "2") (pinfunction "2_2") (pintype "passive"))
    )
    (net (code "54") (name "Net-(LED6-PadA)") (class "Default")
      (node (ref "LED6") (pin "A") (pinfunction "A_A") (pintype "passive"))
      (node (ref "R26") (pin "2") (pinfunction "2_2") (pintype "passive"))
    )
    (net (code "55") (name "Net-(LED7-PadA)") (class "Default")
      (node (ref "LED7") (pin "A") (pinfunction "A_A") (pintype "passive"))
      (node (ref "R27") (pin "2") (pinfunction "2_2") (pintype "passive"))
    )
    (net (code "56") (name "Net-(LED8-PadA)") (class "Default")
      (node (ref "LED8") (pin "A") (pinfunction "A_A") (pintype "passive"))
      (node (ref "R28") (pin "2") (pinfunction "2_2") (pintype "passive"))
    )
    (net (code "57") (name "Net-(LED9-PadA)") (class "Default")
      (node (ref "LED9") (pin "A") (pinfunction "A_A") (pintype "passive"))
      (node (ref "R29") (pin "2") (pinfunction "2_2") (pintype "passive"))
    )
    (net (code "58") (name "Net-(LED10-PadA)") (class "Default")
      (node (ref "LED10") (pin "A") (pinfunction "A_A") (pintype "passive"))
      (node (ref "R30") (pin "2") (pinfunction "2_2") (pintype "passive"))
    )
    (net (code "59") (name "Net-(LED11-PadA)") (class "Default")
      (node (ref "LED11") (pin "A") (pinfunction "A_A") (pintype "passive"))
      (node (ref "R31") (pin "2") (pinfunction "2_2") (pintype "passive"))
    )
    (net (code "60") (name "Net-(LED12-PadA)") (class "Default")
      (node (ref "LED12") (pin "A") (pinfunction "A_A") (pintype "passive"))
      (node (ref "R32") (pin "2") (pinfunction "2_2") (pintype "passive"))
    )
    (net (code "61") (name "Net-(LED13-PadA)") (class "Default")
      (node (ref "LED13") (pin "A") (pinfunction "A_A") (pintype "passive"))
      (node (ref "R33") (pin "2") (pinfunction "2_2") (pintype "passive"))
    )
    (net (code "62") (name "Net-(LED14-PadA)") (class "Default")
      (node (ref "LED14") (pin "A") (pinfunction "A_A") (pintype "passive"))
      (node (ref "R34") (pin "2") (pinfunction "2_2") (pintype "passive"))
    )
    (net (code "63") (name "Net-(LED15-PadA)") (class "Default")
      (node (ref "LED15") (pin "A") (pinfunction "A_A") (pintype "passive"))
      (node (ref "R35") (pin "2") (pinfunction "2_2") (pintype "passive"))
    )
    (net (code "64") (name "Net-(LED16-PadA)") (class "Default")
      (node (ref "LED16") (pin "A") (pinfunction "A_A") (pintype "passive"))
      (node (ref "R36") (pin "2") (pinfunction "2_2") (pintype "passive"))
    )
    (net (code "65") (name "Net-(LED_G-PadA)") (class "Default")
      (node (ref "LED_G") (pin "A") (pinfunction "A_A") (pintype "passive"))
      (node (ref "R9") (pin "1") (pinfunction "1_1") (pintype "passive"))
    )
    (net (code "66") (name "Net-(LED_O-PadA)") (class "Default")
      (node (ref "LED_O") (pin "A") (pinfunction "A_A") (pintype "passive"))
      (node (ref "R11") (pin "1") (pinfunction "1_1") (pintype "passive"))
    )
    (net (code "67") (name "Net-(LED_R-PadA)") (class "Default")
      (node (ref "LED_R") (pin "A") (pinfunction "A_A") (pintype "passive"))
      (node (ref "R10") (pin "1") (pinfunction "1_1") (pintype "passive"))
    )
    (net (code "68") (name "Net-(LED_Y-PadA)") (class "Default")
      (node (ref "LED_Y") (pin "A") (pinfunction "A_A") (pintype "passive"))
      (node (ref "R8") (pin "1") (pinfunction "1_1") (pintype "passive"))
    )
    (net (code "69") (name "Net-(LSP1-PadMP)") (class "Default")
      (node (ref "LSP1") (pin "MP") (pinfunction "MP_MP") (pintype "passive"))
      (node (ref "Q2") (pin "D") (pinfunction "D_D") (pintype "passive"))
      (node (ref "R21") (pin "1") (pinfunction "1_1") (pintype "passive"))
    )
    (net (code "70") (name "Net-(LSP2-PadMP)") (class "Default")
      (node (ref "LSP2") (pin "MP") (pinfunction "MP_MP") (pintype "passive"))
      (node (ref "Q3") (pin "D") (pinfunction "D_D") (pintype "passive"))
      (node (ref "R22") (pin "1") (pinfunction "1_1") (pintype "passive"))
    )
    (net (code "71") (name "Net-(LSP3-PadMP)") (class "Default")
      (node (ref "LSP3") (pin "MP") (pinfunction "MP_MP") (pintype "passive"))
      (node (ref "Q4") (pin "D") (pinfunction "D_D") (pintype "passive"))
      (node (ref "R23") (pin "1") (pinfunction "1_1") (pintype "passive"))
    )
    (net (code "72") (name "Net-(LSP4-PadMP)") (class "Default")
      (node (ref "LSP4") (pin "MP") (pinfunction "MP_MP") (pintype "passive"))
      (node (ref "Q5") (pin "D") (pinfunction "D_D") (pintype "passive"))
      (node (ref "R24") (pin "1") (pinfunction "1_1") (pintype "passive"))
    )
    (net (code "73") (name "Net-(LSP5-PadMP)") (class "Default")
      (node (ref "LSP5") (pin "MP") (pinfunction "MP_MP") (pintype "passive"))
      (node (ref "Q6") (pin "D") (pinfunction "D_D") (pintype "passive"))
      (node (ref "R25") (pin "1") (pinfunction "1_1") (pintype "passive"))
    )
    (net (code "74") (name "Net-(LSP6-PadMP)") (class "Default")
      (node (ref "LSP6") (pin "MP") (pinfunction "MP_MP") (pintype "passive"))
      (node (ref "Q7") (pin "D") (pinfunction "D_D") (pintype "passive"))
      (node (ref "R26") (pin "1") (pinfunction "1_1") (pintype "passive"))
    )
    (net (code "75") (name "Net-(LSP7-PadMP)") (class "Default")
      (node (ref "LSP7") (pin "MP") (pinfunction "MP_MP") (pintype "passive"))
      (node (ref "Q8") (pin "D") (pinfunction "D_D") (pintype "passive"))
      (node (ref "R27") (pin "1") (pinfunction "1_1") (pintype "passive"))
    )
    (net (code "76") (name "Net-(LSP8-PadMP)") (class "Default")
      (node (ref "LSP8") (pin "MP") (pinfunction "MP_MP") (pintype "passive"))
      (node (ref "Q9") (pin "D") (pinfunction "D_D") (pintype "passive"))
      (node (ref "R28") (pin "1") (pinfunction "1_1") (pintype "passive"))
    )
    (net (code "77") (name "Net-(LSP9-PadMP)") (class "Default")
      (node (ref "LSP9") (pin "MP") (pinfunction "MP_MP") (pintype "passive"))
      (node (ref "Q10") (pin "D") (pinfunction "D_D") (pintype "passive"))
      (node (ref "R29") (pin "1") (pinfunction "1_1") (pintype "passive"))
    )
    (net (code "78") (name "Net-(LSP10-PadMP)") (class "Default")
      (node (ref "LSP10") (pin "MP") (pinfunction "MP_MP") (pintype "passive"))
      (node (ref "Q11") (pin "D") (pinfunction "D_D") (pintype "passive"))
      (node (ref "R30") (pin "1") (pinfunction "1_1") (pintype "passive"))
    )
    (net (code "79") (name "Net-(LSP11-PadMP)") (class "Default")
      (node (ref "LSP11") (pin "MP") (pinfunction "MP_MP") (pintype "passive"))
      (node (ref "Q12") (pin "D") (pinfunction "D_D") (pintype "passive"))
      (node (ref "R31") (pin "1") (pinfunction "1_1") (pintype "passive"))
    )
    (net (code "80") (name "Net-(LSP12-PadMP)") (class "Default")
      (node (ref "LSP12") (pin "MP") (pinfunction "MP_MP") (pintype "passive"))
      (node (ref "Q13") (pin "D") (pinfunction "D_D") (pintype "passive"))
      (node (ref "R32") (pin "1") (pinfunction "1_1") (pintype "passive"))
    )
    (net (code "81") (name "Net-(LSP13-PadMP)") (class "Default")
      (node (ref "LSP13") (pin "MP") (pinfunction "MP_MP") (pintype "passive"))
      (node (ref "Q14") (pin "D") (pinfunction "D_D") (pintype "passive"))
      (node (ref "R33") (pin "1") (pinfunction "1_1") (pintype "passive"))
    )
    (net (code "82") (name "Net-(LSP14-PadMP)") (class "Default")
      (node (ref "LSP14") (pin "MP") (pinfunction "MP_MP") (pintype "passive"))
      (node (ref "Q15") (pin "D") (pinfunction "D_D") (pintype "passive"))
      (node (ref "R34") (pin "1") (pinfunction "1_1") (pintype "passive"))
    )
    (net (code "83") (name "Net-(LSP15-PadMP)") (class "Default")
      (node (ref "LSP15") (pin "MP") (pinfunction "MP_MP") (pintype "passive"))
      (node (ref "Q16") (pin "D") (pinfunction "D_D") (pintype "passive"))
      (node (ref "R35") (pin "1") (pinfunction "1_1") (pintype "passive"))
    )
    (net (code "84") (name "Net-(LSP16-PadMP)") (class "Default")
      (node (ref "LSP16") (pin "MP") (pinfunction "MP_MP") (pintype "passive"))
      (node (ref "Q17") (pin "D") (pinfunction "D_D") (pintype "passive"))
      (node (ref "R36") (pin "1") (pinfunction "1_1") (pintype "passive"))
    )
    (net (code "85") (name "Net-(LSP_1-PadMP)") (class "Default")
      (node (ref "LSP_1") (pin "MP") (pinfunction "MP_MP") (pintype "passive"))
      (node (ref "LSP_2") (pin "MP") (pinfunction "MP_MP") (pintype "passive"))
      (node (ref "LSP_3") (pin "MP") (pinfunction "MP_MP") (pintype "passive"))
      (node (ref "LSP_4") (pin "MP") (pinfunction "MP_MP") (pintype "passive"))
      (node (ref "R_Z") (pin "1") (pinfunction "1_1") (pintype "passive"))
    )
    (net (code "86") (name "Net-(Q18-C)") (class "Default")
      (node (ref "Q18") (pin "3") (pinfunction "C_3") (pintype "passive"))
      (node (ref "R14") (pin "2") (pinfunction "2_2") (pintype "passive"))
      (node (ref "T1") (pin "2") (pinfunction "B_2") (pintype "passive"))
      (node (ref "T2") (pin "2") (pinfunction "B_2") (pintype "passive"))
    )
    (net (code "87") (name "Net-(Q18-E)") (class "Default")
      (node (ref "Q18") (pin "1") (pinfunction "E_1") (pintype "passive"))
      (node (ref "R13") (pin "1") (pinfunction "1_1") (pintype "passive"))
    )
    (net (code "88") (name "Net-(Q19-PadD)") (class "Default")
      (node (ref "Q19") (pin "D") (pinfunction "D_D") (pintype "passive"))
      (node (ref "R_Z") (pin "2") (pinfunction "2_2") (pintype "passive"))
      (node (ref "R_Z1") (pin "1") (pinfunction "1_1") (pintype "passive"))
    )
    (net (code "89") (name "Net-(R2-Pad2)") (class "Default")
      (node (ref "R2") (pin "2") (pinfunction "2_2") (pintype "passive"))
      (node (ref "U$4") (pin "DIO2") (pinfunction "DIO2_DIO2") (pintype "bidirectional"))
    )
    (net (code "90") (name "Net-(R4-Pad2)") (class "Default")
      (node (ref "R4") (pin "2") (pinfunction "2_2") (pintype "passive"))
      (node (ref "U$4") (pin "SCK") (pinfunction "SCK_SCK") (pintype "input"))
    )
    (net (code "91") (name "Net-(R5-Pad2)") (class "Default")
      (node (ref "R5") (pin "2") (pinfunction "2_2") (pintype "passive"))
      (node (ref "U$4") (pin "SDO") (pinfunction "SDO_SDO") (pintype "output"))
    )
    (net (code "92") (name "Net-(R6-Pad2)") (class "Default")
      (node (ref "R6") (pin "2") (pinfunction "2_2") (pintype "passive"))
      (node (ref "U$4") (pin "SDI") (pinfunction "SDI_SDI") (pintype "input"))
    )
    (net (code "93") (name "Net-(R17-Pad1)") (class "Default")
      (node (ref "R17") (pin "1") (pinfunction "1_1") (pintype "passive"))
      (node (ref "R3") (pin "1") (pinfunction "1_1") (pintype "passive"))
      (node (ref "U$4") (pin "NRES") (pinfunction "NRES_NRES") (pintype "bidirectional"))
    )
    (net (code "94") (name "RTS") (class "Default")
      (node (ref "IC1") (pin "10") (pinfunction "T2IN_10") (pintype "input"))
      (node (ref "IC2") (pin "4") (pinfunction "PD2(INT0)_4") (pintype "bidirectional"))
    )
    (net (code "95") (name "RX") (class "Default")
      (node (ref "IC1") (pin "12") (pinfunction "R1OUT_12") (pintype "output"))
      (node (ref "IC2") (pin "2") (pinfunction "PD0(RXD)_2") (pintype "bidirectional"))
    )
    (net (code "96") (name "SCK") (class "Default")
      (node (ref "IC2") (pin "19") (pinfunction "PB5(SCK)_19") (pintype "bidirectional"))
      (node (ref "R4") (pin "1") (pinfunction "1_1") (pintype "passive"))
      (node (ref "SV2") (pin "7") (pinfunction "7_7") (pintype "passive"))
    )
    (net (code "97") (name "SHIFT_OE") (class "Default")
      (node (ref "IC2") (pin "24") (pinfunction "PC1(ADC1)_24") (pintype "bidirectional"))
      (node (ref "IC6") (pin "13") (pinfunction "G_13") (pintype "input"))
      (node (ref "IC7") (pin "13") (pinfunction "G_13") (pintype "input"))
      (node (ref "R12") (pin "1") (pinfunction "1_1") (pintype "passive"))
    )
    (net (code "98") (name "SHIFT_RCK") (class "Default")
      (node (ref "IC2") (pin "25") (pinfunction "PC2(ADC2)_25") (pintype "bidirectional"))
      (node (ref "IC6") (pin "12") (pinfunction "RCK_12") (pintype "input"))
      (node (ref "IC7") (pin "12") (pinfunction "RCK_12") (pintype "input"))
    )
    (net (code "99") (name "SHIFT_SCK") (class "Default")
      (node (ref "IC2") (pin "26") (pinfunction "PC3(ADC3)_26") (pintype "bidirectional"))
      (node (ref "IC6") (pin "11") (pinfunction "SCK_11") (pintype "input"))
      (node (ref "IC7") (pin "11") (pinfunction "SCK_11") (pintype "input"))
    )
    (net (code "100") (name "SHIFT_SER") (class "Default")
      (node (ref "IC2") (pin "23") (pinfunction "PC0(ADC0)_23") (pintype "bidirectional"))
      (node (ref "IC6") (pin "14") (pinfunction "SER_14") (pintype "input"))
      (node (ref "R20") (pin "1") (pinfunction "1_1") (pintype "passive"))
    )
    (net (code "101") (name "TX") (class "Default")
      (node (ref "IC1") (pin "11") (pinfunction "T1IN_11") (pintype "input"))
      (node (ref "IC2") (pin "3") (pinfunction "PD1(TXD)_3") (pintype "bidirectional"))
    )
    (net (code "102") (name "V_BATT") (class "Default")
      (node (ref "D3") (pin "A") (pinfunction "A_A") (pintype "passive"))
      (node (ref "PWR_SW2") (pin "MP") (pinfunction "MP_MP") (pintype "passive"))
      (node (ref "R18") (pin "2") (pinfunction "2_2") (pintype "passive"))
      (node (ref "U$3") (pin "VIN") (pinfunction "VIN_VIN") (pintype "bidirectional"))
    )
    (net (code "103") (name "unconnected-(IC7A-QH*-Pad9)") (class "Default")
      (node (ref "IC7") (pin "9") (pinfunction "QH*_9") (pintype "tri_state"))
    )
    (net (code "104") (name "unconnected-(SV2-Pad3)") (class "Default")
      (node (ref "SV2") (pin "3") (pinfunction "3_3") (pintype "passive"))
    )
    (net (code "105") (name "unconnected-(U$4-PadDIO0)") (class "Default")
      (node (ref "U$4") (pin "DIO0") (pinfunction "DIO0_DIO0") (pintype "bidirectional"))
    )
    (net (code "106") (name "unconnected-(U$4-PadDIO1)") (class "Default")
      (node (ref "U$4") (pin "DIO1") (pinfunction "DIO1_DIO1") (pintype "bidirectional"))
    )
    (net (code "107") (name "unconnected-(U$4-PadDIO3)") (class "Default")
      (node (ref "U$4") (pin "DIO3") (pinfunction "DIO3_DIO3") (pintype "bidirectional"))
    )
    (net (code "108") (name "unconnected-(U$4-PadDIO5)") (class "Default")
      (node (ref "U$4") (pin "DIO5") (pinfunction "DIO5_DIO5") (pintype "bidirectional"))
    )
    (net (code "109") (name "{slash}RST") (class "Default")
      (node (ref "C7") (pin "1") (pinfunction "1_1") (pintype "passive"))
      (node (ref "IC2") (pin "1") (pinfunction "PC6(/RESET)_1") (pintype "bidirectional"))
      (node (ref "R1") (pin "1") (pinfunction "1_1") (pintype "passive"))
      (node (ref "SV2") (pin "5") (pinfunction "5_5") (pintype "passive"))
    )
  )
)
